# LEAP_Transmission_Controller_V1_2020-07-.net
KiCad netlist of a schematic drawn in EasyEDA
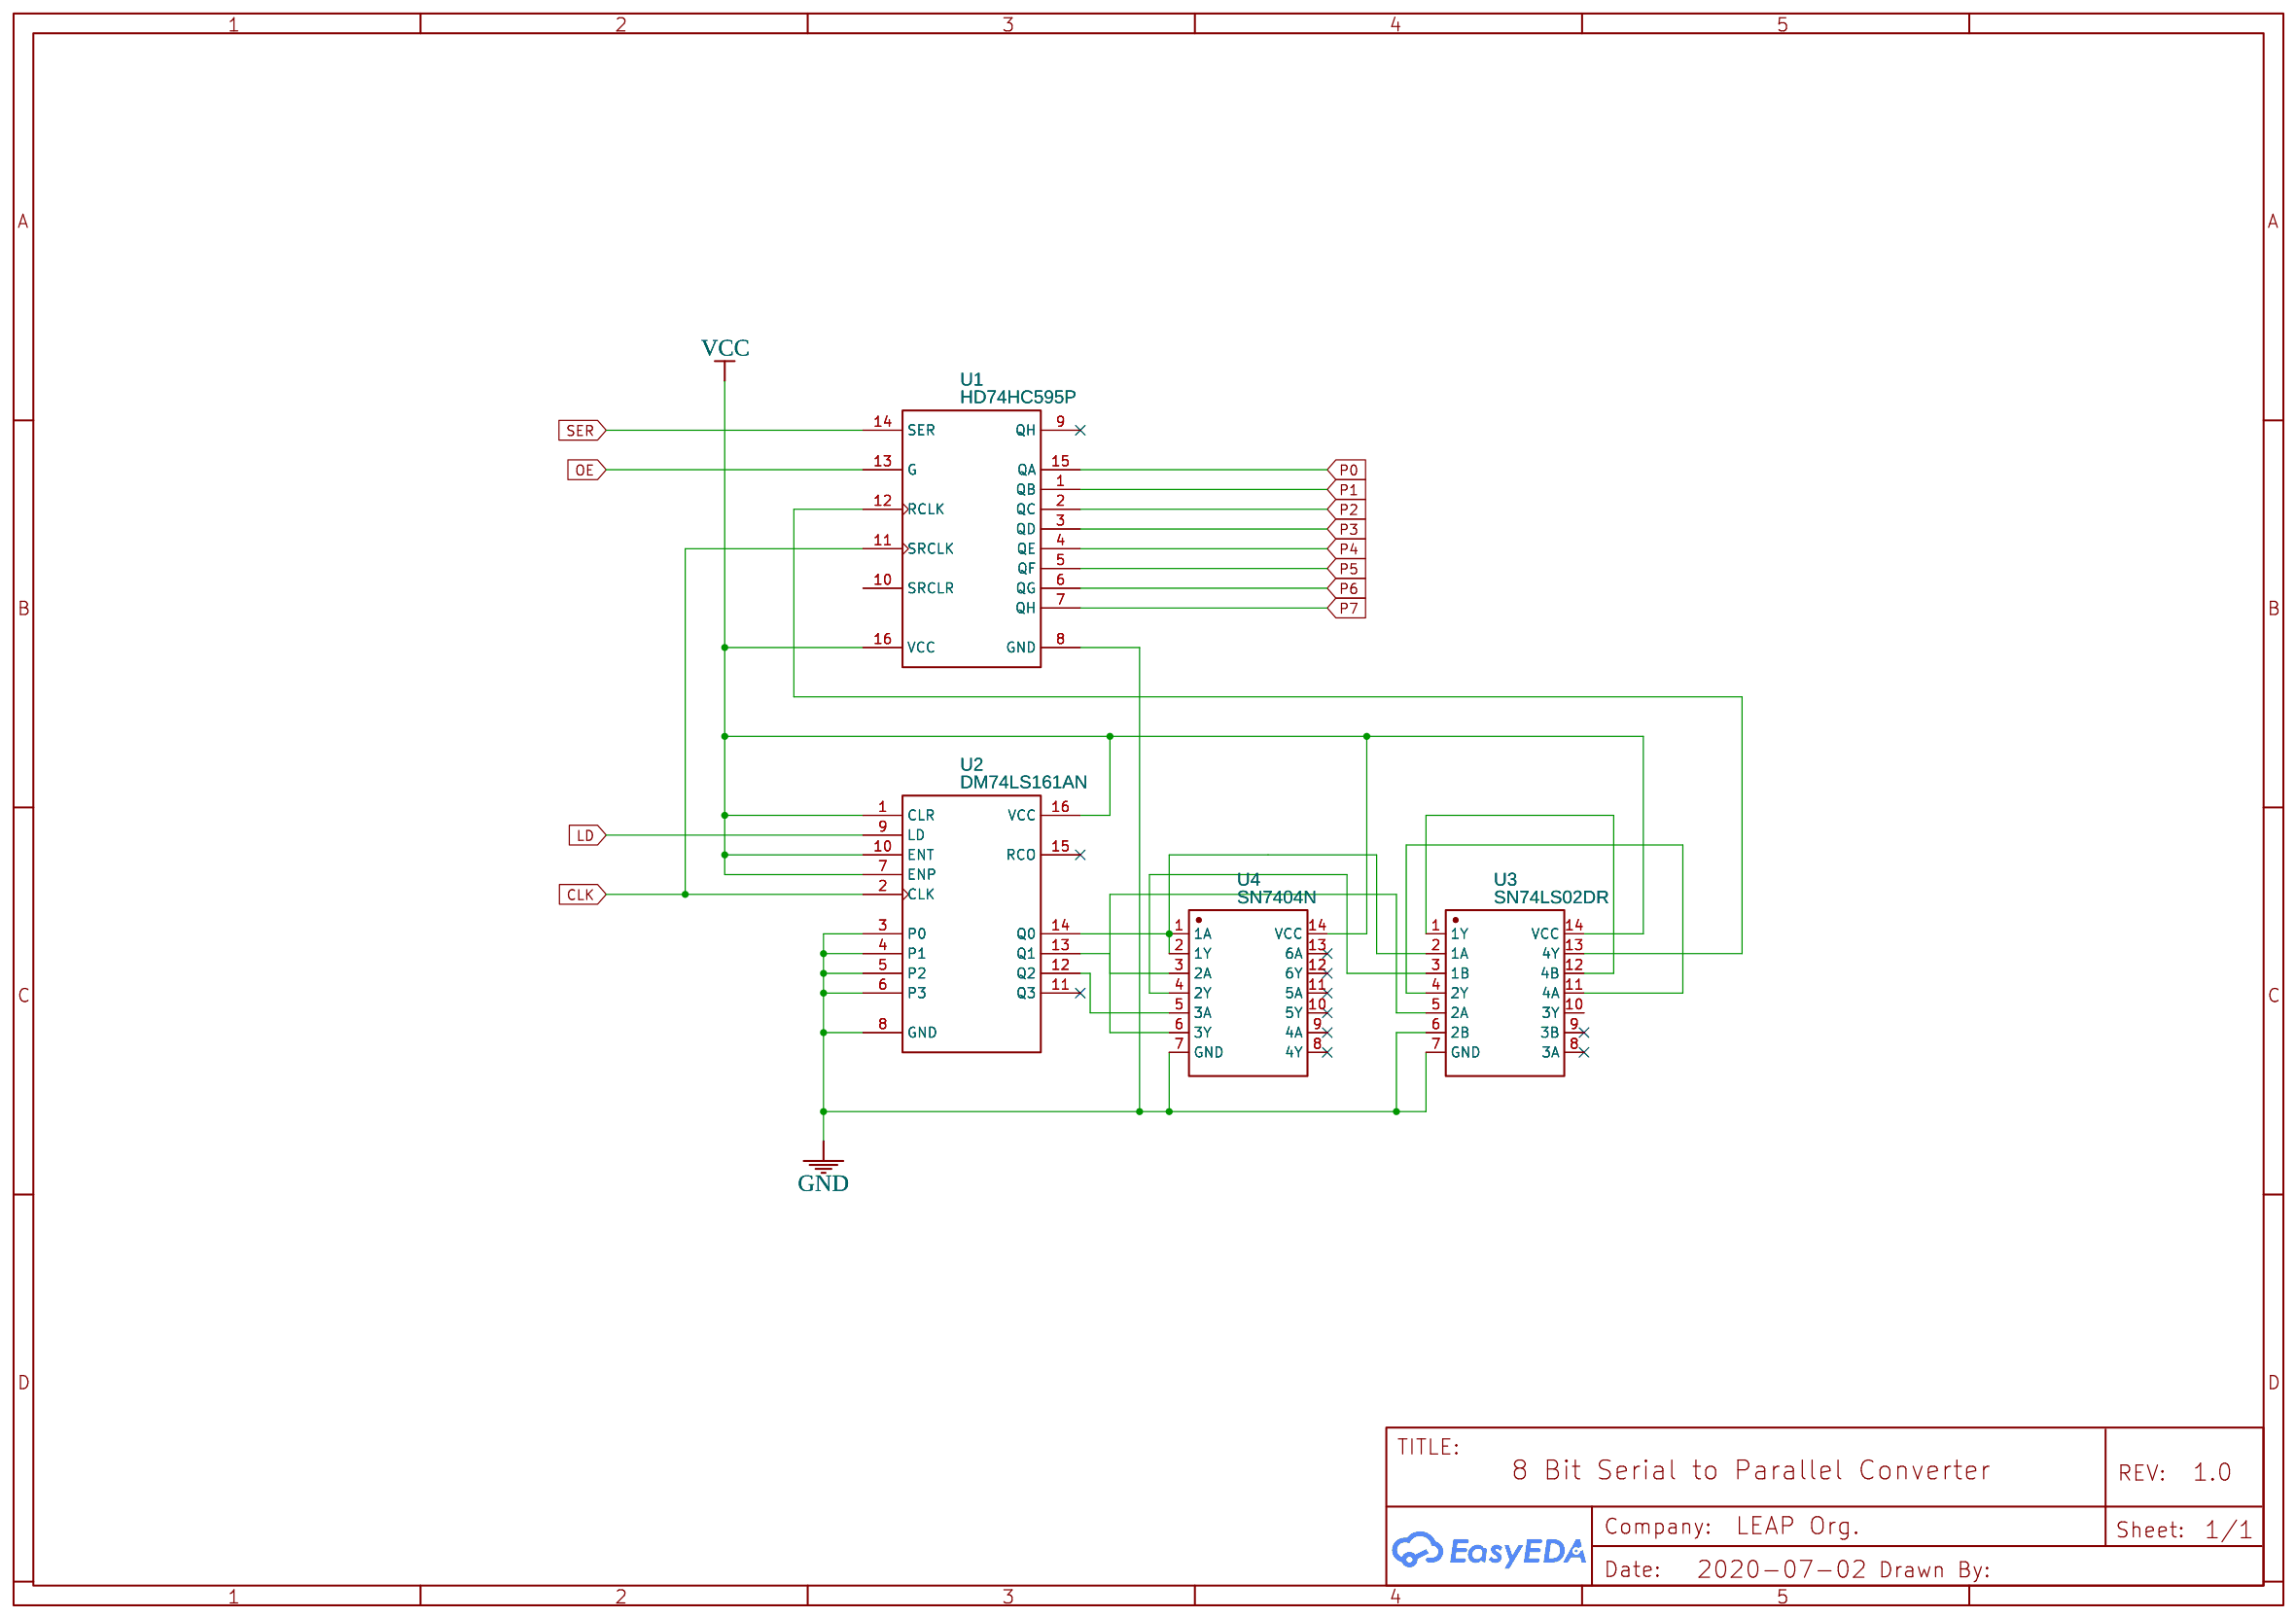
[diagram p0: schematic sheet]

(export (version "E")
  (design (tool "Eeschema 10.0.6"))
  (components
    (comp (ref "U1") (value "HD74HC595P") (libsource (lib "") (part "HD74HC595P")))
    (comp (ref "U2") (value "DM74LS161AN") (libsource (lib "") (part "DM74LS161AN")))
    (comp (ref "U3")
      (value "SN74LS02DR")
      (fields (field (name "BOM_Supplier Part") "C6794"))
      (libsource (lib "") (part "SN74LS02DR"))
    )
    (comp (ref "U4") (value "SN7404N") (libsource (lib "") (part "SN7404N")))
  )
  (nets
    (net (code "1") (name "CLK") (class "Default")
      (node (ref "U1") (pin "11") (pinfunction "SRCLK_11") (pintype "unspecified"))
      (node (ref "U2") (pin "2") (pinfunction "CLK_2") (pintype "unspecified"))
    )
    (net (code "2") (name "GND") (class "Default")
      (node (ref "U1") (pin "8") (pinfunction "GND_8") (pintype "passive"))
      (node (ref "U2") (pin "3") (pinfunction "P0_3") (pintype "unspecified"))
      (node (ref "U2") (pin "4") (pinfunction "P1_4") (pintype "unspecified"))
      (node (ref "U2") (pin "5") (pinfunction "P2_5") (pintype "unspecified"))
      (node (ref "U2") (pin "6") (pinfunction "P3_6") (pintype "unspecified"))
      (node (ref "U2") (pin "8") (pinfunction "GND_8") (pintype "passive"))
      (node (ref "U3") (pin "6") (pinfunction "2B_6") (pintype "unspecified"))
      (node (ref "U3") (pin "7") (pinfunction "GND_7") (pintype "unspecified"))
      (node (ref "U4") (pin "7") (pinfunction "GND_7") (pintype "unspecified"))
    )
    (net (code "3") (name "LD") (class "Default")
      (node (ref "U2") (pin "9") (pinfunction "LD_9") (pintype "unspecified"))
    )
    (net (code "4") (name "Net-(U1-RCLK)") (class "Default")
      (node (ref "U1") (pin "12") (pinfunction "RCLK_12") (pintype "unspecified"))
      (node (ref "U3") (pin "13") (pinfunction "4Y_13") (pintype "unspecified"))
    )
    (net (code "5") (name "Net-(U2-Q0)") (class "Default")
      (node (ref "U2") (pin "14") (pinfunction "Q0_14") (pintype "output"))
      (node (ref "U3") (pin "2") (pinfunction "1A_2") (pintype "unspecified"))
      (node (ref "U4") (pin "1") (pinfunction "1A_1") (pintype "unspecified"))
      (node (ref "U4") (pin "2") (pinfunction "1Y_2") (pintype "unspecified"))
    )
    (net (code "6") (name "Net-(U2-Q1)") (class "Default")
      (node (ref "U2") (pin "13") (pinfunction "Q1_13") (pintype "output"))
      (node (ref "U4") (pin "3") (pinfunction "2A_3") (pintype "unspecified"))
    )
    (net (code "7") (name "Net-(U2-Q2)") (class "Default")
      (node (ref "U2") (pin "12") (pinfunction "Q2_12") (pintype "output"))
      (node (ref "U4") (pin "5") (pinfunction "3A_5") (pintype "unspecified"))
    )
    (net (code "8") (name "Net-(U3-1B)") (class "Default")
      (node (ref "U3") (pin "3") (pinfunction "1B_3") (pintype "unspecified"))
      (node (ref "U4") (pin "4") (pinfunction "2Y_4") (pintype "unspecified"))
    )
    (net (code "9") (name "Net-(U3-1Y)") (class "Default")
      (node (ref "U3") (pin "1") (pinfunction "1Y_1") (pintype "unspecified"))
      (node (ref "U3") (pin "12") (pinfunction "4B_12") (pintype "unspecified"))
    )
    (net (code "10") (name "Net-(U3-2A)") (class "Default")
      (node (ref "U3") (pin "5") (pinfunction "2A_5") (pintype "unspecified"))
      (node (ref "U4") (pin "6") (pinfunction "3Y_6") (pintype "unspecified"))
    )
    (net (code "11") (name "Net-(U3-2Y)") (class "Default")
      (node (ref "U3") (pin "11") (pinfunction "4A_11") (pintype "unspecified"))
      (node (ref "U3") (pin "4") (pinfunction "2Y_4") (pintype "unspecified"))
    )
    (net (code "12") (name "OE") (class "Default")
      (node (ref "U1") (pin "13") (pinfunction "G_13") (pintype "unspecified"))
    )
    (net (code "13") (name "P0") (class "Default")
      (node (ref "U1") (pin "15") (pinfunction "QA_15") (pintype "unspecified"))
    )
    (net (code "14") (name "P1") (class "Default")
      (node (ref "U1") (pin "1") (pinfunction "QB_1") (pintype "unspecified"))
    )
    (net (code "15") (name "P2") (class "Default")
      (node (ref "U1") (pin "2") (pinfunction "QC_2") (pintype "unspecified"))
    )
    (net (code "16") (name "P3") (class "Default")
      (node (ref "U1") (pin "3") (pinfunction "QD_3") (pintype "unspecified"))
    )
    (net (code "17") (name "P4") (class "Default")
      (node (ref "U1") (pin "4") (pinfunction "QE_4") (pintype "unspecified"))
    )
    (net (code "18") (name "P5") (class "Default")
      (node (ref "U1") (pin "5") (pinfunction "QF_5") (pintype "unspecified"))
    )
    (net (code "19") (name "P6") (class "Default")
      (node (ref "U1") (pin "6") (pinfunction "QG_6") (pintype "unspecified"))
    )
    (net (code "20") (name "P7") (class "Default")
      (node (ref "U1") (pin "7") (pinfunction "QH_7") (pintype "unspecified"))
    )
    (net (code "21") (name "SER") (class "Default")
      (node (ref "U1") (pin "14") (pinfunction "SER_14") (pintype "unspecified"))
    )
    (net (code "22") (name "VCC") (class "Default")
      (node (ref "U1") (pin "16") (pinfunction "VCC_16") (pintype "passive"))
      (node (ref "U2") (pin "1") (pinfunction "CLR_1") (pintype "unspecified"))
      (node (ref "U2") (pin "10") (pinfunction "ENT_10") (pintype "unspecified"))
      (node (ref "U2") (pin "16") (pinfunction "VCC_16") (pintype "passive"))
      (node (ref "U2") (pin "7") (pinfunction "ENP_7") (pintype "unspecified"))
      (node (ref "U3") (pin "14") (pinfunction "VCC_14") (pintype "unspecified"))
      (node (ref "U4") (pin "14") (pinfunction "VCC_14") (pintype "unspecified"))
    )
    (net (code "23") (name "unconnected-(U1-QH-Pad9)") (class "Default")
      (node (ref "U1") (pin "9") (pinfunction "QH_9") (pintype "output+no_connect"))
    )
    (net (code "24") (name "unconnected-(U1-SRCLR-Pad10)") (class "Default")
      (node (ref "U1") (pin "10") (pinfunction "SRCLR_10") (pintype "unspecified"))
    )
    (net (code "25") (name "unconnected-(U2-Q3-Pad11)") (class "Default")
      (node (ref "U2") (pin "11") (pinfunction "Q3_11") (pintype "output+no_connect"))
    )
    (net (code "26") (name "unconnected-(U2-RCO-Pad15)") (class "Default")
      (node (ref "U2") (pin "15") (pinfunction "RCO_15") (pintype "output+no_connect"))
    )
    (net (code "27") (name "unconnected-(U3-3A-Pad8)") (class "Default")
      (node (ref "U3") (pin "8") (pinfunction "3A_8") (pintype "unspecified+no_connect"))
    )
    (net (code "28") (name "unconnected-(U3-3B-Pad9)") (class "Default")
      (node (ref "U3") (pin "9") (pinfunction "3B_9") (pintype "unspecified+no_connect"))
    )
    (net (code "29") (name "unconnected-(U3-3Y-Pad10)") (class "Default")
      (node (ref "U3") (pin "10") (pinfunction "3Y_10") (pintype "unspecified"))
    )
    (net (code "30") (name "unconnected-(U4-4A-Pad9)") (class "Default")
      (node (ref "U4") (pin "9") (pinfunction "4A_9") (pintype "unspecified+no_connect"))
    )
    (net (code "31") (name "unconnected-(U4-4Y-Pad8)") (class "Default")
      (node (ref "U4") (pin "8") (pinfunction "4Y_8") (pintype "unspecified+no_connect"))
    )
    (net (code "32") (name "unconnected-(U4-5A-Pad11)") (class "Default")
      (node (ref "U4") (pin "11") (pinfunction "5A_11") (pintype "unspecified+no_connect"))
    )
    (net (code "33") (name "unconnected-(U4-5Y-Pad10)") (class "Default")
      (node (ref "U4") (pin "10") (pinfunction "5Y_10") (pintype "unspecified+no_connect"))
    )
    (net (code "34") (name "unconnected-(U4-6A-Pad13)") (class "Default")
      (node (ref "U4") (pin "13") (pinfunction "6A_13") (pintype "unspecified+no_connect"))
    )
    (net (code "35") (name "unconnected-(U4-6Y-Pad12)") (class "Default")
      (node (ref "U4") (pin "12") (pinfunction "6Y_12") (pintype "unspecified+no_connect"))
    )
  )
)
